# PROC010C_PMIC_Reference.net
KiCad netlist of a schematic drawn in Altium Designer
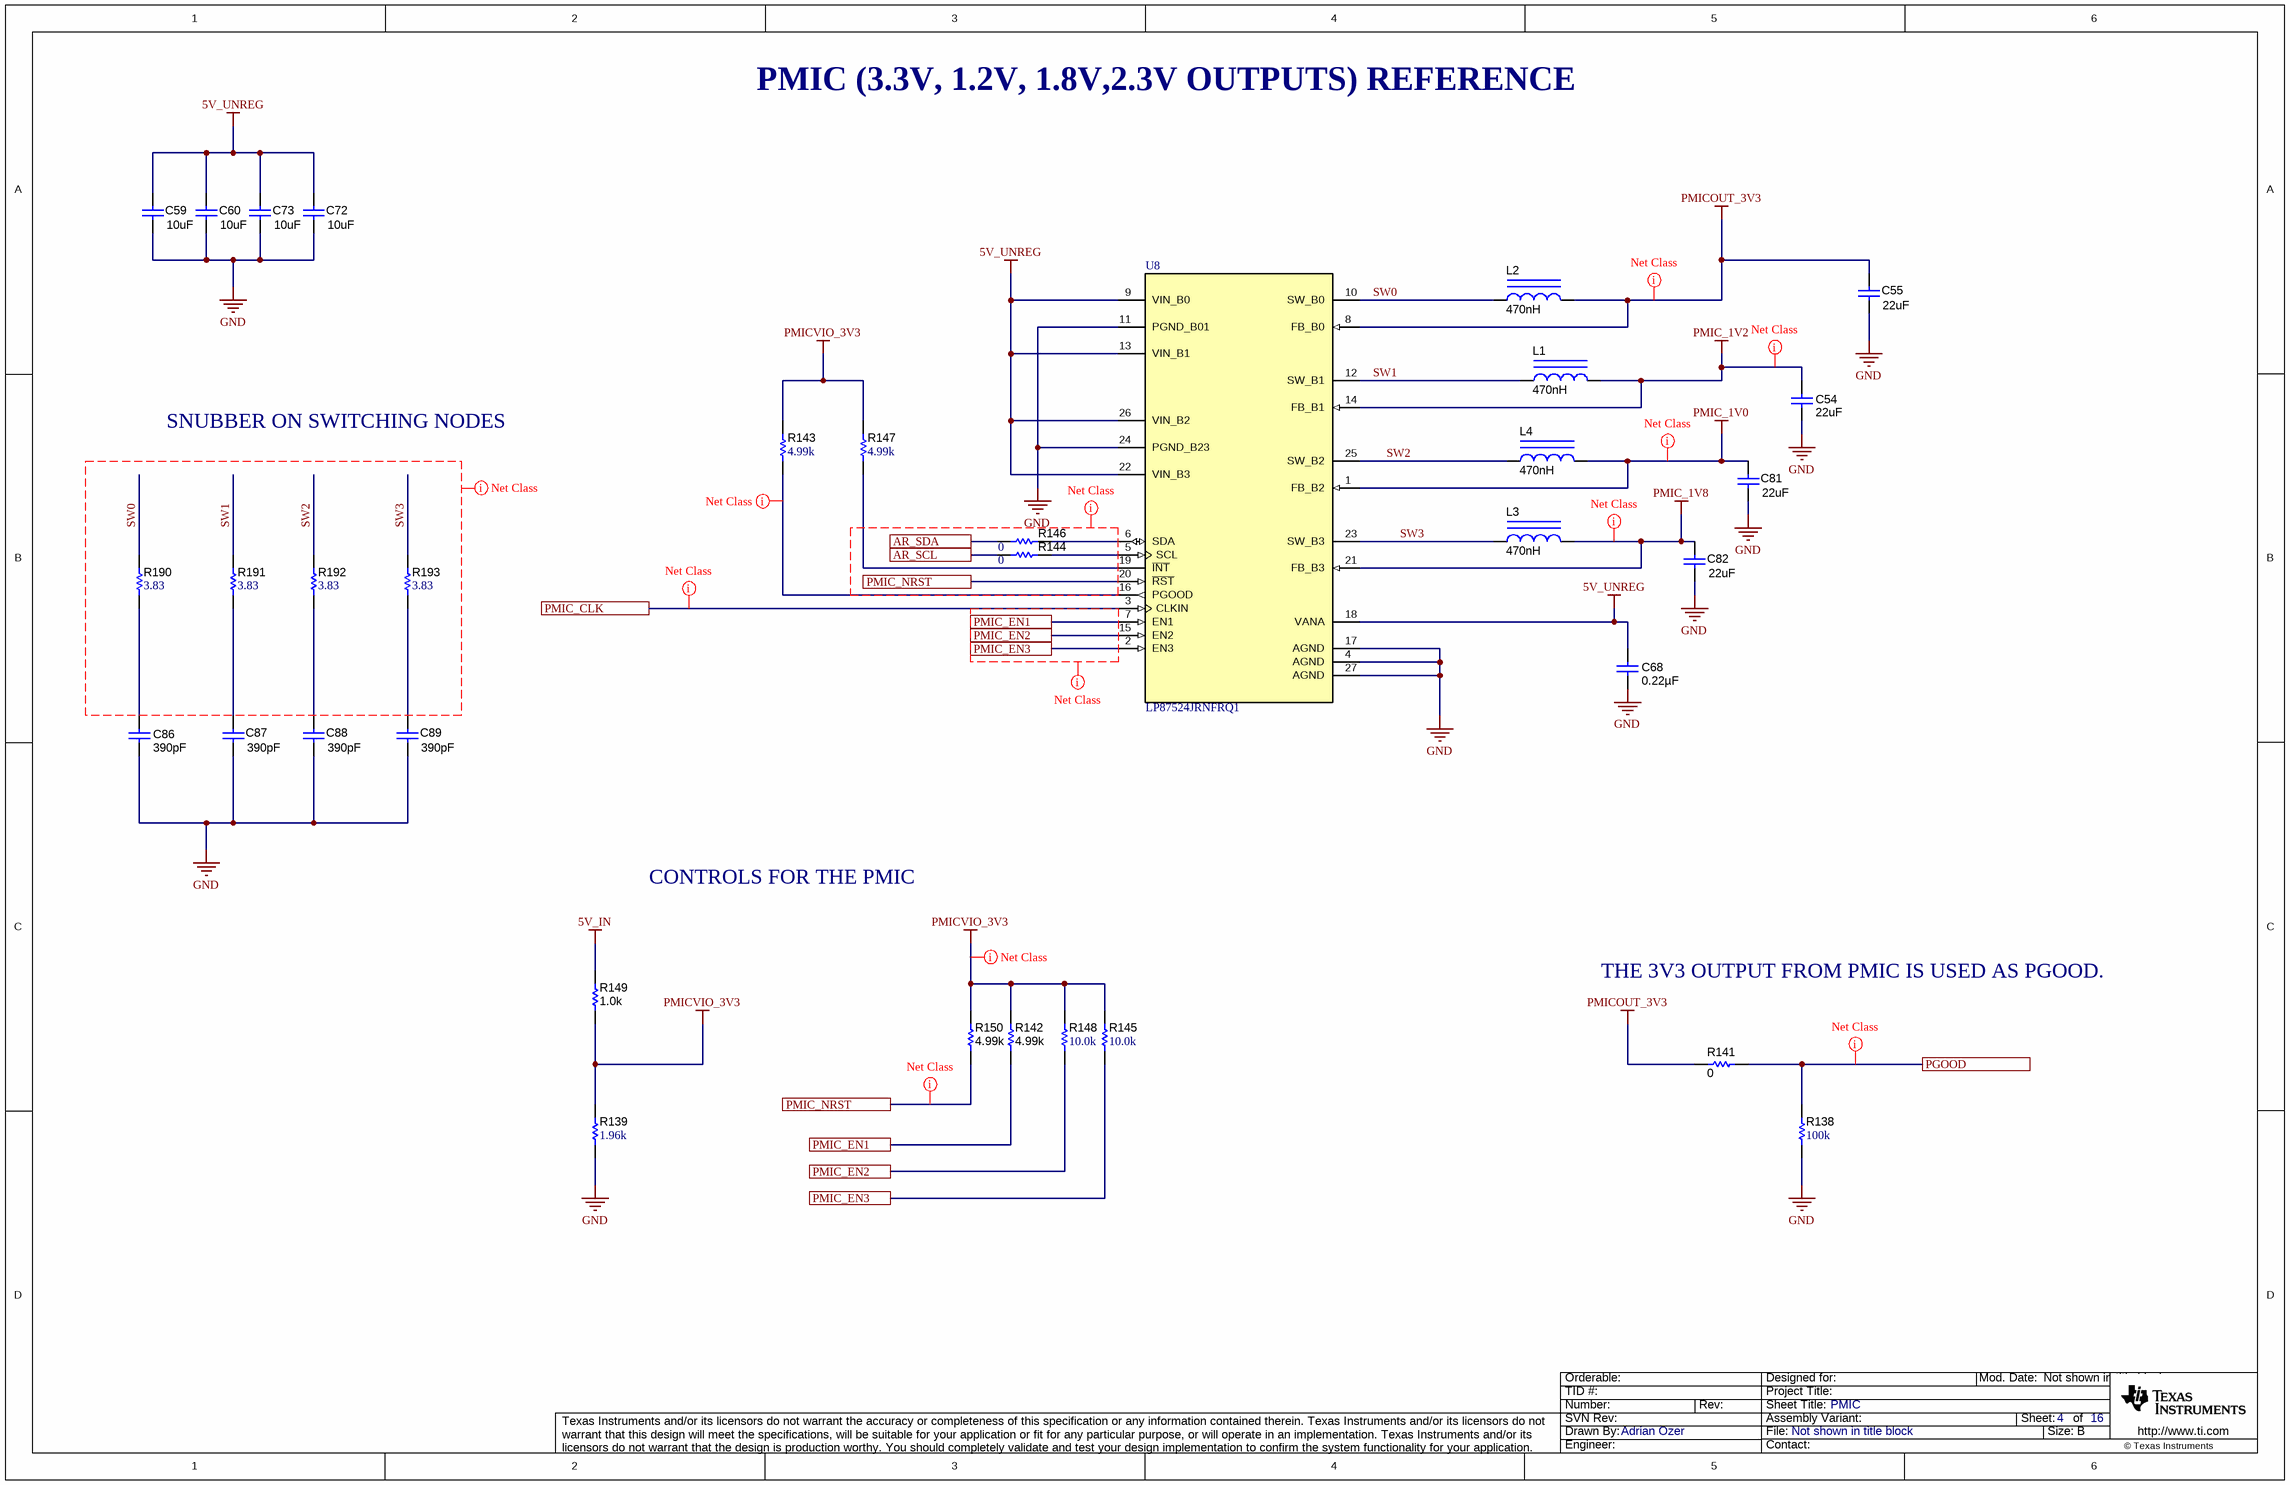
[diagram p0: PROC010C_PMIC_Reference.SchDoc]

(export (version "E")
  (design (tool "Eeschema 10.0.6"))
  (components
    (comp (ref "C54")
      (value "GCM31CR71A226KE02")
      (footprint "1206_180")
      (description "CAP, CERM, 22 uF, 10 V, +/- 10%, X7R, AEC-Q200 Grade 1, 1206")
      (fields
        (field (name "MANUFACTURER") "MuRata")
        (field (name "VALUEDISPLAYED") "22uF")
        (field (name "PUBLISHER") "Texas Instruments")
      )
      (libsource (lib "Altium Vault - TI") (part "CMP-0008811-2"))
    )
    (comp (ref "C55")
      (value "GCM31CR71A226KE02")
      (footprint "1206_180")
      (description "CAP, CERM, 22 uF, 10 V, +/- 10%, X7R, AEC-Q200 Grade 1, 1206")
      (fields
        (field (name "MANUFACTURER") "MuRata")
        (field (name "VALUEDISPLAYED") "22uF")
        (field (name "PUBLISHER") "Texas Instruments")
      )
      (libsource (lib "Altium Vault - TI") (part "Capacitor"))
    )
    (comp (ref "C59")
      (value "GCM21BR71A106KE22L")
      (footprint "0805_HV1")
      (description "CAP, CERM, 10 uF, 10 V, +/- 10%, X7R, 0805")
      (fields
        (field (name "MANUFACTURER") "MuRata")
        (field (name "VALUEDISPLAYED") "10uF")
        (field (name "PUBLISHER") "Texas Instruments")
      )
      (libsource (lib "Altium Vault - TI") (part "CMP-0008017-2"))
    )
    (comp (ref "C60")
      (value "GCM21BR71A106KE22L")
      (footprint "0805_HV1")
      (description "CAP, CERM, 10 uF, 10 V, +/- 10%, X7R, 0805")
      (fields
        (field (name "MANUFACTURER") "MuRata")
        (field (name "VALUEDISPLAYED") "10uF")
        (field (name "PUBLISHER") "Texas Instruments")
      )
      (libsource (lib "Altium Vault - TI") (part "CMP-0008017-2"))
    )
    (comp (ref "C68")
      (value "GCM155R71C224KE02D")
      (footprint "0402L")
      (description "CAP, CERM, 0.22 µF, 16 V,+/- 10%, X7R, AEC-Q200 Grade 1, 0402")
      (fields (field (name "MANUFACTURER") "MuRata") (field (name "VALUEDISPLAYED") "0.22µF"))
      (libsource (lib "Altium Vault - TI") (part "CMP-0078265-1"))
    )
    (comp (ref "C72")
      (value "GCM21BR71A106KE22L")
      (footprint "0805_HV1")
      (description "CAP, CERM, 10 uF, 10 V, +/- 10%, X7R, 0805")
      (fields
        (field (name "MANUFACTURER") "MuRata")
        (field (name "VALUEDISPLAYED") "10uF")
        (field (name "PUBLISHER") "Texas Instruments")
      )
      (libsource (lib "Altium Vault - TI") (part "CMP-0008017-2"))
    )
    (comp (ref "C73")
      (value "GCM21BR71A106KE22L")
      (footprint "0805_HV1")
      (description "CAP, CERM, 10 uF, 10 V, +/- 10%, X7R, 0805")
      (fields
        (field (name "MANUFACTURER") "MuRata")
        (field (name "VALUEDISPLAYED") "10uF")
        (field (name "PUBLISHER") "Texas Instruments")
      )
      (libsource (lib "Altium Vault - TI") (part "CMP-0008017-2"))
    )
    (comp (ref "C81")
      (value "GCM31CR71A226KE02")
      (footprint "1206_180")
      (description "CAP, CERM, 22 uF, 10 V, +/- 10%, X7R, AEC-Q200 Grade 1, 1206")
      (fields
        (field (name "MANUFACTURER") "MuRata")
        (field (name "VALUEDISPLAYED") "22uF")
        (field (name "PUBLISHER") "Texas Instruments")
      )
      (libsource (lib "Altium Vault - TI") (part "Capacitor"))
    )
    (comp (ref "C82")
      (value "GCM31CR71A226KE02")
      (footprint "1206_180")
      (description "CAP, CERM, 22 uF, 10 V, +/- 10%, X7R, AEC-Q200 Grade 1, 1206")
      (fields
        (field (name "MANUFACTURER") "MuRata")
        (field (name "VALUEDISPLAYED") "22uF")
        (field (name "PUBLISHER") "Texas Instruments")
      )
      (libsource (lib "Altium Vault - TI") (part "Capacitor"))
    )
    (comp (ref "C86")
      (value "CGA2B2NP01H391J050BA")
      (footprint "0402L")
      (description "CAP, CERM, 390 pF, 50 V,+/- 5%, C0G/NP0, AEC-Q200 Grade 0, 0402")
      (fields (field (name "MANUFACTURER") "TDK") (field (name "VALUEDISPLAYED") "390pF"))
      (libsource (lib "Altium Vault - TI") (part "Capacitor"))
    )
    (comp (ref "C87")
      (value "CGA2B2NP01H391J050BA")
      (footprint "0402L")
      (description "CAP, CERM, 390 pF, 50 V,+/- 5%, C0G/NP0, AEC-Q200 Grade 0, 0402")
      (fields (field (name "MANUFACTURER") "TDK") (field (name "VALUEDISPLAYED") "390pF"))
      (libsource (lib "Altium Vault - TI") (part "Capacitor"))
    )
    (comp (ref "C88")
      (value "CGA2B2NP01H391J050BA")
      (footprint "0402L")
      (description "CAP, CERM, 390 pF, 50 V,+/- 5%, C0G/NP0, AEC-Q200 Grade 0, 0402")
      (fields (field (name "MANUFACTURER") "TDK") (field (name "VALUEDISPLAYED") "390pF"))
      (libsource (lib "Altium Vault - TI") (part "Capacitor"))
    )
    (comp (ref "C89")
      (value "CGA2B2NP01H391J050BA")
      (footprint "0402L")
      (description "CAP, CERM, 390 pF, 50 V,+/- 5%, C0G/NP0, AEC-Q200 Grade 0, 0402")
      (fields (field (name "MANUFACTURER") "TDK") (field (name "VALUEDISPLAYED") "390pF"))
      (libsource (lib "Altium Vault - TI") (part "Capacitor"))
    )
    (comp (ref "L1")
      (value "DFE252012P-R47M=P2")
      (footprint "DFE252012P")
      (description "Inductor, Shielded, 470 nH, 4.7 A, 0.021 ohm, SMD")
      (fields
        (field (name "MANUFACTURER") "MuRata Toko")
        (field (name "VALUEDISPLAYED") "470nH")
        (field (name "PUBLISHER") "Texas Instruments")
      )
      (libsource (lib "Altium Vault - TI") (part "Inductor_Iron"))
    )
    (comp (ref "L2")
      (value "DFE252012P-R47M=P2")
      (footprint "DFE252012P")
      (description "Inductor, Shielded, 470 nH, 4.7 A, 0.021 ohm, SMD")
      (fields
        (field (name "MANUFACTURER") "MuRata Toko")
        (field (name "VALUEDISPLAYED") "470nH")
        (field (name "PUBLISHER") "Texas Instruments")
      )
      (libsource (lib "Altium Vault - TI") (part "Inductor_Iron"))
    )
    (comp (ref "L3")
      (value "DFE252012P-R47M=P2")
      (footprint "DFE252012P")
      (description "Inductor, Shielded, 470 nH, 4.7 A, 0.021 ohm, SMD")
      (fields
        (field (name "MANUFACTURER") "MuRata Toko")
        (field (name "VALUEDISPLAYED") "470nH")
        (field (name "PUBLISHER") "Texas Instruments")
      )
      (libsource (lib "Altium Vault - TI") (part "Inductor_Iron"))
    )
    (comp (ref "L4")
      (value "DFE252012P-R47M=P2")
      (footprint "DFE252012P")
      (description "Inductor, Shielded, 470 nH, 4.7 A, 0.021 ohm, SMD")
      (fields
        (field (name "MANUFACTURER") "MuRata Toko")
        (field (name "VALUEDISPLAYED") "470nH")
        (field (name "PUBLISHER") "Texas Instruments")
      )
      (libsource (lib "Altium Vault - TI") (part "Inductor_Iron"))
    )
    (comp (ref "R138")
      (value "CRCW0402100KFKED")
      (footprint "0402L")
      (description "RES, 100 k, 1%, 0.063 W, AEC-Q200 Grade 0, 0402")
      (fields (field (name "MANUFACTURER") "Vishay-Dale") (field (name "VALUEDISPLAYED") "100k"))
      (libsource (lib "Altium Vault - TI") (part "Resistor"))
    )
    (comp (ref "R139")
      (value "CRCW04021K96FKED")
      (footprint "0402L")
      (description "RES, 1.96 k, 1%, 0.063 W, AEC-Q200 Grade 0, 0402")
      (fields (field (name "MANUFACTURER") "Vishay-Dale") (field (name "VALUEDISPLAYED") "1.96k"))
      (libsource (lib "Altium Vault - TI") (part "Resistor"))
    )
    (comp (ref "R141")
      (value "ERJ-2GE0R00X")
      (footprint "0402L")
      (description "RES, 0, 5%, 0.063 W, 0402")
      (fields
        (field (name "MANUFACTURER") "Panasonic")
        (field (name "VALUEDISPLAYED") "0")
        (field (name "PUBLISHER") "Texas Instruments")
      )
      (libsource (lib "Altium Vault - TI") (part "Resistor"))
    )
    (comp (ref "R142")
      (value "ERJ-2RKF4991X")
      (footprint "0402L")
      (description "RES, 4.99 k, 1%, 0.1 W, AEC-Q200 Grade 0, 0402")
      (fields
        (field (name "MANUFACTURER") "Panasonic")
        (field (name "VALUEDISPLAYED") "4.99k")
        (field (name "PUBLISHER") "Texas Instruments")
      )
      (libsource (lib "Altium Vault - TI") (part "Resistor"))
    )
    (comp (ref "R143")
      (value "CRCW04024K99FKED")
      (footprint "0402L")
      (description "RES, 4.99 k, 1%, 0.063 W, AEC-Q200 Grade 0, 0402")
      (fields (field (name "MANUFACTURER") "Vishay-Dale") (field (name "VALUEDISPLAYED") "4.99k"))
      (libsource (lib "Altium Vault - TI") (part "Resistor"))
    )
    (comp (ref "R144")
      (value "CRCW02010000Z0ED")
      (footprint "0201_Silk")
      (description "RES, 0, 5%, 0.05 W, 0201")
      (fields (field (name "MANUFACTURER") "Vishay-Dale") (field (name "VALUEDISPLAYED") "0"))
      (libsource (lib "Altium Vault - TI") (part "Resistor"))
    )
    (comp (ref "R145")
      (value "CRCW040210K0FKED")
      (footprint "0402L")
      (description "RES, 10.0 k, 1%, 0.063 W, AEC-Q200 Grade 0, 0402")
      (fields (field (name "MANUFACTURER") "Vishay-Dale") (field (name "VALUEDISPLAYED") "10.0k"))
      (libsource (lib "Altium Vault - TI") (part "CMP-0025958-3"))
    )
    (comp (ref "R146")
      (value "CRCW02010000Z0ED")
      (footprint "0201_Silk")
      (description "RES, 0, 5%, 0.05 W, 0201")
      (fields (field (name "MANUFACTURER") "Vishay-Dale") (field (name "VALUEDISPLAYED") "0"))
      (libsource (lib "Altium Vault - TI") (part "Resistor"))
    )
    (comp (ref "R147")
      (value "CRCW04024K99FKED")
      (footprint "0402L")
      (description "RES, 4.99 k, 1%, 0.063 W, AEC-Q200 Grade 0, 0402")
      (fields (field (name "MANUFACTURER") "Vishay-Dale") (field (name "VALUEDISPLAYED") "4.99k"))
      (libsource (lib "Altium Vault - TI") (part "Resistor"))
    )
    (comp (ref "R148")
      (value "CRCW040210K0FKED")
      (footprint "0402L")
      (description "RES, 10.0 k, 1%, 0.063 W, AEC-Q200 Grade 0, 0402")
      (fields (field (name "MANUFACTURER") "Vishay-Dale") (field (name "VALUEDISPLAYED") "10.0k"))
      (libsource (lib "Altium Vault - TI") (part "Resistor"))
    )
    (comp (ref "R149")
      (value "ERJ-2GEJ102X")
      (footprint "0402L")
      (description "RES, 1.0 k, 5%, 0.1 W, AEC-Q200 Grade 0, 0402")
      (fields (field (name "MANUFACTURER") "Panasonic") (field (name "VALUEDISPLAYED") "1.0k"))
      (libsource (lib "Altium Vault - TI") (part "Resistor"))
    )
    (comp (ref "R150")
      (value "ERJ-2RKF4991X")
      (footprint "0402L")
      (description "RES, 4.99 k, 1%, 0.1 W, AEC-Q200 Grade 0, 0402")
      (fields
        (field (name "MANUFACTURER") "Panasonic")
        (field (name "VALUEDISPLAYED") "4.99k")
        (field (name "PUBLISHER") "Texas Instruments")
      )
      (libsource (lib "Altium Vault - TI") (part "Resistor"))
    )
    (comp (ref "R190")
      (value "CRCW04023R83FKED")
      (footprint "0402L")
      (description "RES, 3.83, 1%, 0.063 W, AEC-Q200 Grade 0, 0402")
      (fields (field (name "MANUFACTURER") "Vishay-Dale") (field (name "VALUEDISPLAYED") "3.83"))
      (libsource (lib "Altium Vault - TI") (part "Resistor"))
    )
    (comp (ref "R191")
      (value "CRCW04023R83FKED")
      (footprint "0402L")
      (description "RES, 3.83, 1%, 0.063 W, AEC-Q200 Grade 0, 0402")
      (fields (field (name "MANUFACTURER") "Vishay-Dale") (field (name "VALUEDISPLAYED") "3.83"))
      (libsource (lib "Altium Vault - TI") (part "Resistor"))
    )
    (comp (ref "R192")
      (value "CRCW04023R83FKED")
      (footprint "0402L")
      (description "RES, 3.83, 1%, 0.063 W, AEC-Q200 Grade 0, 0402")
      (fields (field (name "MANUFACTURER") "Vishay-Dale") (field (name "VALUEDISPLAYED") "3.83"))
      (libsource (lib "Altium Vault - TI") (part "Resistor"))
    )
    (comp (ref "R193")
      (value "CRCW04023R83FKED")
      (footprint "0402L")
      (description "RES, 3.83, 1%, 0.063 W, AEC-Q200 Grade 0, 0402")
      (fields (field (name "MANUFACTURER") "Vishay-Dale") (field (name "VALUEDISPLAYED") "3.83"))
      (libsource (lib "Altium Vault - TI") (part "Resistor"))
    )
    (comp (ref "U8")
      (value "LP87524JRNFRQ1")
      (footprint "RNF0026C")
      (description "4-A + 2.5-A + Two 1.5-A Buck Converters With Integrated Switches, RNF0026C (VQFN-HR-26)")
      (fields
        (field (name "ALTERNATE PARTNUMBER") "LP87524JRNFTQ1")
        (field (name "MANUFACTURER") "Texas Instruments")
        (field (name "PARTNUMBER") "LP87524JRNFRQ1")
      )
      (libsource (lib "Altium Vault - TI") (part "CMP-0079120-1"))
    )
  )
  (nets
    (net (code "1") (name "/AR_SCL") (class "Default")
      (node (ref "R144") (pin "1") (pinfunction "1_1") (pintype "passive"))
    )
    (net (code "2") (name "/AR_SDA") (class "Default")
      (node (ref "R146") (pin "2") (pinfunction "2_2") (pintype "passive"))
    )
    (net (code "3") (name "/PGOOD") (class "Default")
      (node (ref "R138") (pin "2") (pinfunction "2_2") (pintype "passive"))
      (node (ref "R141") (pin "2") (pinfunction "2_2") (pintype "passive"))
    )
    (net (code "4") (name "/PMIC_CLK") (class "Default")
      (node (ref "U8") (pin "3") (pinfunction "CLKIN_3") (pintype "input"))
    )
    (net (code "5") (name "/PMIC_EN1") (class "Default")
      (node (ref "R142") (pin "1") (pinfunction "1_1") (pintype "passive"))
      (node (ref "U8") (pin "7") (pinfunction "EN1_7") (pintype "input"))
    )
    (net (code "6") (name "/PMIC_EN2") (class "Default")
      (node (ref "R148") (pin "1") (pinfunction "1_1") (pintype "passive"))
      (node (ref "U8") (pin "15") (pinfunction "EN2_15") (pintype "input"))
    )
    (net (code "7") (name "/PMIC_EN3") (class "Default")
      (node (ref "R145") (pin "1") (pinfunction "1_1") (pintype "passive"))
      (node (ref "U8") (pin "2") (pinfunction "EN3_2") (pintype "input"))
    )
    (net (code "8") (name "/PMIC_NRST") (class "Default")
      (node (ref "R150") (pin "2") (pinfunction "2_2") (pintype "passive"))
      (node (ref "U8") (pin "20") (pinfunction "RST_20") (pintype "input"))
    )
    (net (code "9") (name "/SW0") (class "Default")
      (node (ref "L2") (pin "1") (pinfunction "1_1") (pintype "passive"))
      (node (ref "R190") (pin "2") (pinfunction "2_2") (pintype "passive"))
      (node (ref "U8") (pin "10") (pinfunction "SW_B0_10") (pintype "power_in"))
    )
    (net (code "10") (name "/SW1") (class "Default")
      (node (ref "L1") (pin "1") (pinfunction "1_1") (pintype "passive"))
      (node (ref "R191") (pin "2") (pinfunction "2_2") (pintype "passive"))
      (node (ref "U8") (pin "12") (pinfunction "SW_B1_12") (pintype "power_in"))
    )
    (net (code "11") (name "/SW2") (class "Default")
      (node (ref "L4") (pin "1") (pinfunction "1_1") (pintype "passive"))
      (node (ref "R192") (pin "2") (pinfunction "2_2") (pintype "passive"))
      (node (ref "U8") (pin "25") (pinfunction "SW_B2_25") (pintype "power_in"))
    )
    (net (code "12") (name "/SW3") (class "Default")
      (node (ref "L3") (pin "1") (pinfunction "1_1") (pintype "passive"))
      (node (ref "R193") (pin "2") (pinfunction "2_2") (pintype "passive"))
      (node (ref "U8") (pin "23") (pinfunction "SW_B3_23") (pintype "power_in"))
    )
    (net (code "13") (name "5V_IN") (class "Default")
      (node (ref "R149") (pin "2") (pinfunction "2_2") (pintype "passive"))
    )
    (net (code "14") (name "5V_UNREG") (class "Default")
      (node (ref "C59") (pin "2") (pinfunction "2_2") (pintype "passive"))
      (node (ref "C60") (pin "2") (pinfunction "2_2") (pintype "passive"))
      (node (ref "C68") (pin "2") (pinfunction "2_2") (pintype "passive"))
      (node (ref "C72") (pin "2") (pinfunction "2_2") (pintype "passive"))
      (node (ref "C73") (pin "2") (pinfunction "2_2") (pintype "passive"))
      (node (ref "U8") (pin "13") (pinfunction "VIN_B1_13") (pintype "power_in"))
      (node (ref "U8") (pin "18") (pinfunction "VANA_18") (pintype "power_in"))
      (node (ref "U8") (pin "22") (pinfunction "VIN_B3_22") (pintype "power_in"))
      (node (ref "U8") (pin "26") (pinfunction "VIN_B2_26") (pintype "power_in"))
      (node (ref "U8") (pin "9") (pinfunction "VIN_B0_9") (pintype "power_in"))
    )
    (net (code "15") (name "GND") (class "Default")
      (node (ref "C54") (pin "1") (pinfunction "1_1") (pintype "passive"))
      (node (ref "C55") (pin "1") (pinfunction "1_1") (pintype "passive"))
      (node (ref "C59") (pin "1") (pinfunction "1_1") (pintype "passive"))
      (node (ref "C60") (pin "1") (pinfunction "1_1") (pintype "passive"))
      (node (ref "C68") (pin "1") (pinfunction "1_1") (pintype "passive"))
      (node (ref "C72") (pin "1") (pinfunction "1_1") (pintype "passive"))
      (node (ref "C73") (pin "1") (pinfunction "1_1") (pintype "passive"))
      (node (ref "C81") (pin "1") (pinfunction "1_1") (pintype "passive"))
      (node (ref "C82") (pin "1") (pinfunction "1_1") (pintype "passive"))
      (node (ref "C86") (pin "1") (pinfunction "1_1") (pintype "passive"))
      (node (ref "C87") (pin "1") (pinfunction "1_1") (pintype "passive"))
      (node (ref "C88") (pin "1") (pinfunction "1_1") (pintype "passive"))
      (node (ref "C89") (pin "1") (pinfunction "1_1") (pintype "passive"))
      (node (ref "R138") (pin "1") (pinfunction "1_1") (pintype "passive"))
      (node (ref "R139") (pin "1") (pinfunction "1_1") (pintype "passive"))
      (node (ref "U8") (pin "11") (pinfunction "PGND_B01_11") (pintype "power_in"))
      (node (ref "U8") (pin "17") (pinfunction "AGND_17") (pintype "power_in"))
      (node (ref "U8") (pin "24") (pinfunction "PGND_B23_24") (pintype "power_in"))
      (node (ref "U8") (pin "27") (pinfunction "AGND_27") (pintype "power_in"))
      (node (ref "U8") (pin "4") (pinfunction "AGND_4") (pintype "power_in"))
    )
    (net (code "16") (name "Net-(C86-Pad2)") (class "Default")
      (node (ref "C86") (pin "2") (pinfunction "2_2") (pintype "passive"))
      (node (ref "R190") (pin "1") (pinfunction "1_1") (pintype "passive"))
    )
    (net (code "17") (name "Net-(C87-Pad2)") (class "Default")
      (node (ref "C87") (pin "2") (pinfunction "2_2") (pintype "passive"))
      (node (ref "R191") (pin "1") (pinfunction "1_1") (pintype "passive"))
    )
    (net (code "18") (name "Net-(C88-Pad2)") (class "Default")
      (node (ref "C88") (pin "2") (pinfunction "2_2") (pintype "passive"))
      (node (ref "R192") (pin "1") (pinfunction "1_1") (pintype "passive"))
    )
    (net (code "19") (name "Net-(C89-Pad2)") (class "Default")
      (node (ref "C89") (pin "2") (pinfunction "2_2") (pintype "passive"))
      (node (ref "R193") (pin "1") (pinfunction "1_1") (pintype "passive"))
    )
    (net (code "20") (name "Net-(U8-INT)") (class "Default")
      (node (ref "R147") (pin "1") (pinfunction "1_1") (pintype "passive"))
      (node (ref "U8") (pin "19") (pinfunction "INT_19") (pintype "open_collector"))
    )
    (net (code "21") (name "Net-(U8-PGOOD)") (class "Default")
      (node (ref "R143") (pin "1") (pinfunction "1_1") (pintype "passive"))
      (node (ref "U8") (pin "16") (pinfunction "PGOOD_16") (pintype "output"))
    )
    (net (code "22") (name "Net-(U8-SCL)") (class "Default")
      (node (ref "R144") (pin "2") (pinfunction "2_2") (pintype "passive"))
      (node (ref "U8") (pin "5") (pinfunction "SCL_5") (pintype "input"))
    )
    (net (code "23") (name "Net-(U8-SDA)") (class "Default")
      (node (ref "R146") (pin "1") (pinfunction "1_1") (pintype "passive"))
      (node (ref "U8") (pin "6") (pinfunction "SDA_6") (pintype "bidirectional"))
    )
    (net (code "24") (name "PMICOUT_3V3") (class "Default")
      (node (ref "C55") (pin "2") (pinfunction "2_2") (pintype "passive"))
      (node (ref "L2") (pin "2") (pinfunction "2_2") (pintype "passive"))
      (node (ref "R141") (pin "1") (pinfunction "1_1") (pintype "passive"))
      (node (ref "U8") (pin "8") (pinfunction "FB_B0_8") (pintype "input"))
    )
    (net (code "25") (name "PMICVIO_3V3") (class "Default")
      (node (ref "R139") (pin "2") (pinfunction "2_2") (pintype "passive"))
      (node (ref "R142") (pin "2") (pinfunction "2_2") (pintype "passive"))
      (node (ref "R143") (pin "2") (pinfunction "2_2") (pintype "passive"))
      (node (ref "R145") (pin "2") (pinfunction "2_2") (pintype "passive"))
      (node (ref "R147") (pin "2") (pinfunction "2_2") (pintype "passive"))
      (node (ref "R148") (pin "2") (pinfunction "2_2") (pintype "passive"))
      (node (ref "R149") (pin "1") (pinfunction "1_1") (pintype "passive"))
      (node (ref "R150") (pin "1") (pinfunction "1_1") (pintype "passive"))
    )
    (net (code "26") (name "PMIC_1V0") (class "Default")
      (node (ref "C81") (pin "2") (pinfunction "2_2") (pintype "passive"))
      (node (ref "L4") (pin "2") (pinfunction "2_2") (pintype "passive"))
      (node (ref "U8") (pin "1") (pinfunction "FB_B2_1") (pintype "input"))
    )
    (net (code "27") (name "PMIC_1V2") (class "Default")
      (node (ref "C54") (pin "2") (pinfunction "2_2") (pintype "passive"))
      (node (ref "L1") (pin "2") (pinfunction "2_2") (pintype "passive"))
      (node (ref "U8") (pin "14") (pinfunction "FB_B1_14") (pintype "input"))
    )
    (net (code "28") (name "PMIC_1V8") (class "Default")
      (node (ref "C82") (pin "2") (pinfunction "2_2") (pintype "passive"))
      (node (ref "L3") (pin "2") (pinfunction "2_2") (pintype "passive"))
      (node (ref "U8") (pin "21") (pinfunction "FB_B3_21") (pintype "input"))
    )
  )
)
